# Schmetic.net
KiCad netlist of a schematic drawn in EAGLE
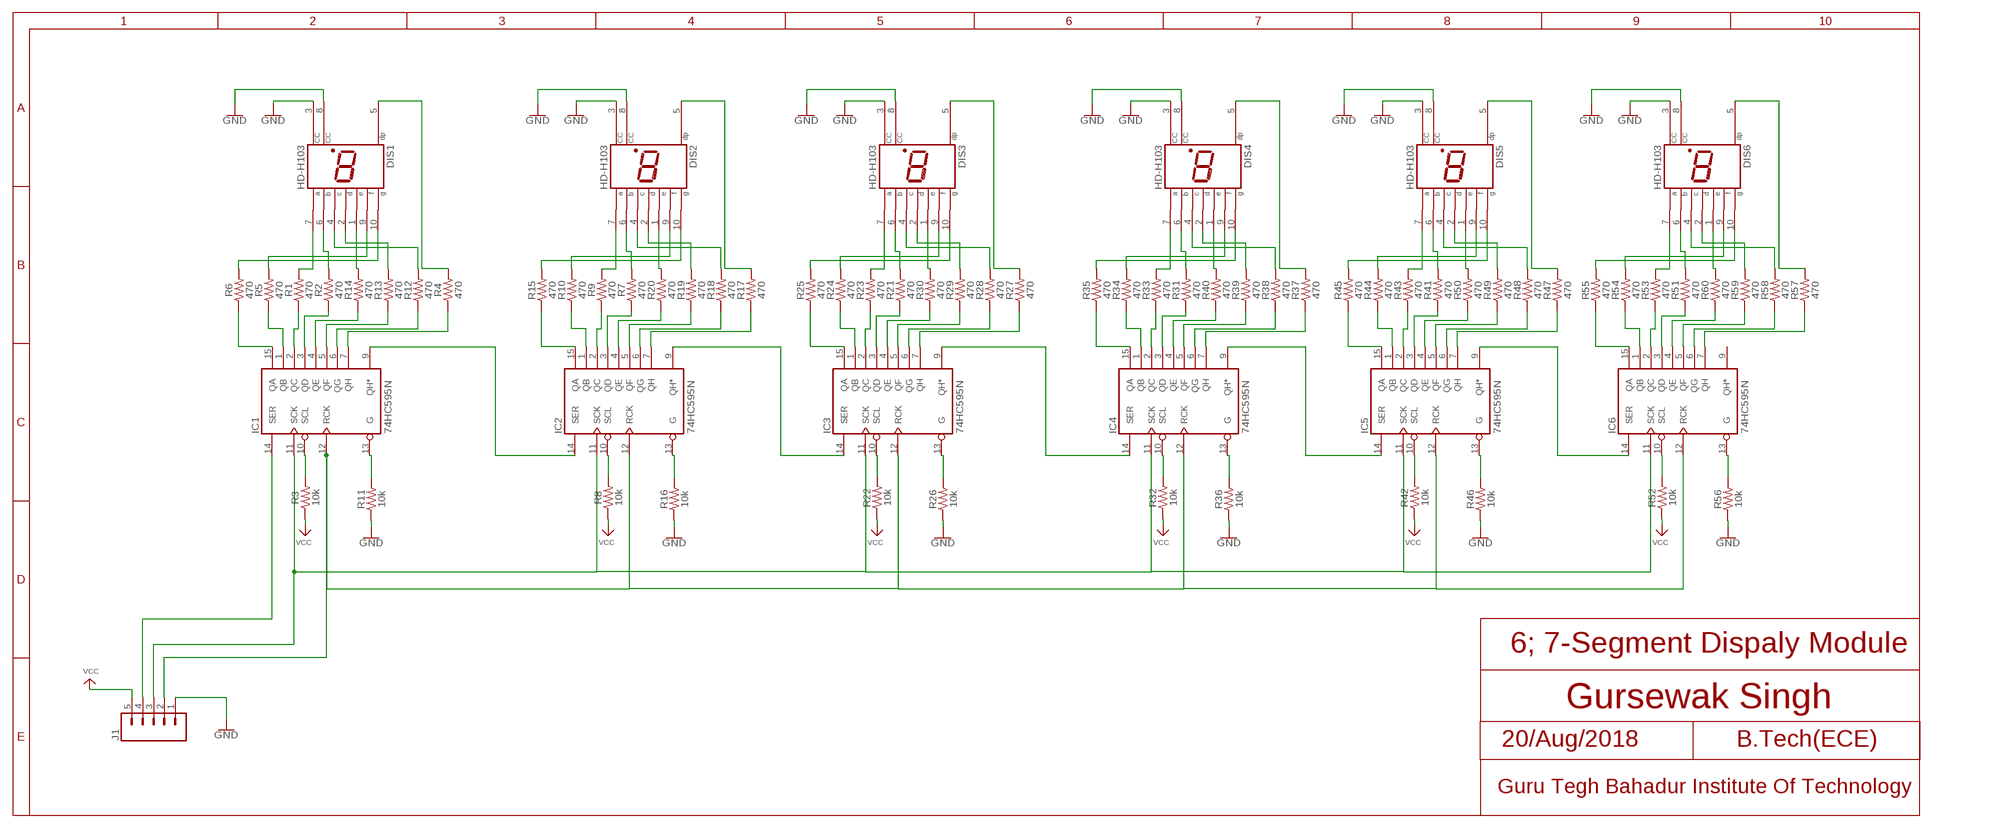
[diagram p0: schematic, sheet 1]

(export (version "E")
  (design (tool "Eeschema 10.0.6"))
  (components
    (comp (ref "DIS1")
      (value "HD-H103")
      (footprint "eagle-import:HDSP-M")
      (libsource (lib "eagle-import") (part "HD-H103"))
    )
    (comp (ref "DIS2")
      (value "HD-H103")
      (footprint "eagle-import:HDSP-M")
      (libsource (lib "eagle-import") (part "HD-H103"))
    )
    (comp (ref "DIS3")
      (value "HD-H103")
      (footprint "eagle-import:HDSP-M")
      (libsource (lib "eagle-import") (part "HD-H103"))
    )
    (comp (ref "DIS4")
      (value "HD-H103")
      (footprint "eagle-import:HDSP-M")
      (libsource (lib "eagle-import") (part "HD-H103"))
    )
    (comp (ref "DIS5")
      (value "HD-H103")
      (footprint "eagle-import:HDSP-M")
      (libsource (lib "eagle-import") (part "HD-H103"))
    )
    (comp (ref "DIS6")
      (value "HD-H103")
      (footprint "eagle-import:HDSP-M")
      (libsource (lib "eagle-import") (part "HD-H103"))
    )
    (comp (ref "IC1")
      (value "74HC595N")
      (footprint "eagle-import:DIL16")
      (libsource (lib "eagle-import") (part "74595NHC"))
    )
    (comp (ref "IC2")
      (value "74HC595N")
      (footprint "eagle-import:DIL16")
      (libsource (lib "eagle-import") (part "74595NHC"))
    )
    (comp (ref "IC3")
      (value "74HC595N")
      (footprint "eagle-import:DIL16")
      (libsource (lib "eagle-import") (part "74595NHC"))
    )
    (comp (ref "IC4")
      (value "74HC595N")
      (footprint "eagle-import:DIL16")
      (libsource (lib "eagle-import") (part "74595NHC"))
    )
    (comp (ref "IC5")
      (value "74HC595N")
      (footprint "eagle-import:DIL16")
      (libsource (lib "eagle-import") (part "74595NHC"))
    )
    (comp (ref "IC6")
      (value "74HC595N")
      (footprint "eagle-import:DIL16")
      (libsource (lib "eagle-import") (part "74595NHC"))
    )
    (comp (ref "J1")
      (value "CONN_05LOCK_LONGPADS")
      (footprint "eagle-import:1X05_LOCK_LONGPADS")
      (libsource (lib "eagle-import") (part "CONN_05LOCK_LONGPADS"))
    )
    (comp (ref "R1")
      (value "470")
      (footprint "eagle-import:AXIAL-0.3")
      (libsource (lib "eagle-import") (part "1KOHM-HORIZ-1/4W-1%"))
    )
    (comp (ref "R2")
      (value "470")
      (footprint "eagle-import:AXIAL-0.3")
      (libsource (lib "eagle-import") (part "1KOHM-HORIZ-1/4W-1%"))
    )
    (comp (ref "R3")
      (value "10k")
      (footprint "eagle-import:AXIAL-0.3")
      (libsource (lib "eagle-import") (part "1KOHM-HORIZ-1/4W-1%"))
    )
    (comp (ref "R4")
      (value "470")
      (footprint "eagle-import:AXIAL-0.3")
      (libsource (lib "eagle-import") (part "1KOHM-HORIZ-1/4W-1%"))
    )
    (comp (ref "R5")
      (value "470")
      (footprint "eagle-import:AXIAL-0.3")
      (libsource (lib "eagle-import") (part "1KOHM-HORIZ-1/4W-1%"))
    )
    (comp (ref "R6")
      (value "470")
      (footprint "eagle-import:AXIAL-0.3")
      (libsource (lib "eagle-import") (part "1KOHM-HORIZ-1/4W-1%"))
    )
    (comp (ref "R7")
      (value "470")
      (footprint "eagle-import:AXIAL-0.3")
      (libsource (lib "eagle-import") (part "1KOHM-HORIZ-1/4W-1%"))
    )
    (comp (ref "R8")
      (value "10k")
      (footprint "eagle-import:AXIAL-0.3")
      (libsource (lib "eagle-import") (part "1KOHM-HORIZ-1/4W-1%"))
    )
    (comp (ref "R9")
      (value "470")
      (footprint "eagle-import:AXIAL-0.3")
      (libsource (lib "eagle-import") (part "1KOHM-HORIZ-1/4W-1%"))
    )
    (comp (ref "R10")
      (value "470")
      (footprint "eagle-import:AXIAL-0.3")
      (libsource (lib "eagle-import") (part "1KOHM-HORIZ-1/4W-1%"))
    )
    (comp (ref "R11")
      (value "10k")
      (footprint "eagle-import:AXIAL-0.3")
      (libsource (lib "eagle-import") (part "1KOHM-HORIZ-1/4W-1%"))
    )
    (comp (ref "R12")
      (value "470")
      (footprint "eagle-import:AXIAL-0.3")
      (libsource (lib "eagle-import") (part "1KOHM-HORIZ-1/4W-1%"))
    )
    (comp (ref "R13")
      (value "470")
      (footprint "eagle-import:AXIAL-0.3")
      (libsource (lib "eagle-import") (part "1KOHM-HORIZ-1/4W-1%"))
    )
    (comp (ref "R14")
      (value "470")
      (footprint "eagle-import:AXIAL-0.3")
      (libsource (lib "eagle-import") (part "1KOHM-HORIZ-1/4W-1%"))
    )
    (comp (ref "R15")
      (value "470")
      (footprint "eagle-import:AXIAL-0.3")
      (libsource (lib "eagle-import") (part "1KOHM-HORIZ-1/4W-1%"))
    )
    (comp (ref "R16")
      (value "10k")
      (footprint "eagle-import:AXIAL-0.3")
      (libsource (lib "eagle-import") (part "1KOHM-HORIZ-1/4W-1%"))
    )
    (comp (ref "R17")
      (value "470")
      (footprint "eagle-import:AXIAL-0.3")
      (libsource (lib "eagle-import") (part "1KOHM-HORIZ-1/4W-1%"))
    )
    (comp (ref "R18")
      (value "470")
      (footprint "eagle-import:AXIAL-0.3")
      (libsource (lib "eagle-import") (part "1KOHM-HORIZ-1/4W-1%"))
    )
    (comp (ref "R19")
      (value "470")
      (footprint "eagle-import:AXIAL-0.3")
      (libsource (lib "eagle-import") (part "1KOHM-HORIZ-1/4W-1%"))
    )
    (comp (ref "R20")
      (value "470")
      (footprint "eagle-import:AXIAL-0.3")
      (libsource (lib "eagle-import") (part "1KOHM-HORIZ-1/4W-1%"))
    )
    (comp (ref "R21")
      (value "470")
      (footprint "eagle-import:AXIAL-0.3")
      (libsource (lib "eagle-import") (part "1KOHM-HORIZ-1/4W-1%"))
    )
    (comp (ref "R22")
      (value "10k")
      (footprint "eagle-import:AXIAL-0.3")
      (libsource (lib "eagle-import") (part "1KOHM-HORIZ-1/4W-1%"))
    )
    (comp (ref "R23")
      (value "470")
      (footprint "eagle-import:AXIAL-0.3")
      (libsource (lib "eagle-import") (part "1KOHM-HORIZ-1/4W-1%"))
    )
    (comp (ref "R24")
      (value "470")
      (footprint "eagle-import:AXIAL-0.3")
      (libsource (lib "eagle-import") (part "1KOHM-HORIZ-1/4W-1%"))
    )
    (comp (ref "R25")
      (value "470")
      (footprint "eagle-import:AXIAL-0.3")
      (libsource (lib "eagle-import") (part "1KOHM-HORIZ-1/4W-1%"))
    )
    (comp (ref "R26")
      (value "10k")
      (footprint "eagle-import:AXIAL-0.3")
      (libsource (lib "eagle-import") (part "1KOHM-HORIZ-1/4W-1%"))
    )
    (comp (ref "R27")
      (value "470")
      (footprint "eagle-import:AXIAL-0.3")
      (libsource (lib "eagle-import") (part "1KOHM-HORIZ-1/4W-1%"))
    )
    (comp (ref "R28")
      (value "470")
      (footprint "eagle-import:AXIAL-0.3")
      (libsource (lib "eagle-import") (part "1KOHM-HORIZ-1/4W-1%"))
    )
    (comp (ref "R29")
      (value "470")
      (footprint "eagle-import:AXIAL-0.3")
      (libsource (lib "eagle-import") (part "1KOHM-HORIZ-1/4W-1%"))
    )
    (comp (ref "R30")
      (value "470")
      (footprint "eagle-import:AXIAL-0.3")
      (libsource (lib "eagle-import") (part "1KOHM-HORIZ-1/4W-1%"))
    )
    (comp (ref "R31")
      (value "470")
      (footprint "eagle-import:AXIAL-0.3")
      (libsource (lib "eagle-import") (part "1KOHM-HORIZ-1/4W-1%"))
    )
    (comp (ref "R32")
      (value "10k")
      (footprint "eagle-import:AXIAL-0.3")
      (libsource (lib "eagle-import") (part "1KOHM-HORIZ-1/4W-1%"))
    )
    (comp (ref "R33")
      (value "470")
      (footprint "eagle-import:AXIAL-0.3")
      (libsource (lib "eagle-import") (part "1KOHM-HORIZ-1/4W-1%"))
    )
    (comp (ref "R34")
      (value "470")
      (footprint "eagle-import:AXIAL-0.3")
      (libsource (lib "eagle-import") (part "1KOHM-HORIZ-1/4W-1%"))
    )
    (comp (ref "R35")
      (value "470")
      (footprint "eagle-import:AXIAL-0.3")
      (libsource (lib "eagle-import") (part "1KOHM-HORIZ-1/4W-1%"))
    )
    (comp (ref "R36")
      (value "10k")
      (footprint "eagle-import:AXIAL-0.3")
      (libsource (lib "eagle-import") (part "1KOHM-HORIZ-1/4W-1%"))
    )
    (comp (ref "R37")
      (value "470")
      (footprint "eagle-import:AXIAL-0.3")
      (libsource (lib "eagle-import") (part "1KOHM-HORIZ-1/4W-1%"))
    )
    (comp (ref "R38")
      (value "470")
      (footprint "eagle-import:AXIAL-0.3")
      (libsource (lib "eagle-import") (part "1KOHM-HORIZ-1/4W-1%"))
    )
    (comp (ref "R39")
      (value "470")
      (footprint "eagle-import:AXIAL-0.3")
      (libsource (lib "eagle-import") (part "1KOHM-HORIZ-1/4W-1%"))
    )
    (comp (ref "R40")
      (value "470")
      (footprint "eagle-import:AXIAL-0.3")
      (libsource (lib "eagle-import") (part "1KOHM-HORIZ-1/4W-1%"))
    )
    (comp (ref "R41")
      (value "470")
      (footprint "eagle-import:AXIAL-0.3")
      (libsource (lib "eagle-import") (part "1KOHM-HORIZ-1/4W-1%"))
    )
    (comp (ref "R42")
      (value "10k")
      (footprint "eagle-import:AXIAL-0.3")
      (libsource (lib "eagle-import") (part "1KOHM-HORIZ-1/4W-1%"))
    )
    (comp (ref "R43")
      (value "470")
      (footprint "eagle-import:AXIAL-0.3")
      (libsource (lib "eagle-import") (part "1KOHM-HORIZ-1/4W-1%"))
    )
    (comp (ref "R44")
      (value "470")
      (footprint "eagle-import:AXIAL-0.3")
      (libsource (lib "eagle-import") (part "1KOHM-HORIZ-1/4W-1%"))
    )
    (comp (ref "R45")
      (value "470")
      (footprint "eagle-import:AXIAL-0.3")
      (libsource (lib "eagle-import") (part "1KOHM-HORIZ-1/4W-1%"))
    )
    (comp (ref "R46")
      (value "10k")
      (footprint "eagle-import:AXIAL-0.3")
      (libsource (lib "eagle-import") (part "1KOHM-HORIZ-1/4W-1%"))
    )
    (comp (ref "R47")
      (value "470")
      (footprint "eagle-import:AXIAL-0.3")
      (libsource (lib "eagle-import") (part "1KOHM-HORIZ-1/4W-1%"))
    )
    (comp (ref "R48")
      (value "470")
      (footprint "eagle-import:AXIAL-0.3")
      (libsource (lib "eagle-import") (part "1KOHM-HORIZ-1/4W-1%"))
    )
    (comp (ref "R49")
      (value "470")
      (footprint "eagle-import:AXIAL-0.3")
      (libsource (lib "eagle-import") (part "1KOHM-HORIZ-1/4W-1%"))
    )
    (comp (ref "R50")
      (value "470")
      (footprint "eagle-import:AXIAL-0.3")
      (libsource (lib "eagle-import") (part "1KOHM-HORIZ-1/4W-1%"))
    )
    (comp (ref "R51")
      (value "470")
      (footprint "eagle-import:AXIAL-0.3")
      (libsource (lib "eagle-import") (part "1KOHM-HORIZ-1/4W-1%"))
    )
    (comp (ref "R52")
      (value "10k")
      (footprint "eagle-import:AXIAL-0.3")
      (libsource (lib "eagle-import") (part "1KOHM-HORIZ-1/4W-1%"))
    )
    (comp (ref "R53")
      (value "470")
      (footprint "eagle-import:AXIAL-0.3")
      (libsource (lib "eagle-import") (part "1KOHM-HORIZ-1/4W-1%"))
    )
    (comp (ref "R54")
      (value "470")
      (footprint "eagle-import:AXIAL-0.3")
      (libsource (lib "eagle-import") (part "1KOHM-HORIZ-1/4W-1%"))
    )
    (comp (ref "R55")
      (value "470")
      (footprint "eagle-import:AXIAL-0.3")
      (libsource (lib "eagle-import") (part "1KOHM-HORIZ-1/4W-1%"))
    )
    (comp (ref "R56")
      (value "10k")
      (footprint "eagle-import:AXIAL-0.3")
      (libsource (lib "eagle-import") (part "1KOHM-HORIZ-1/4W-1%"))
    )
    (comp (ref "R57")
      (value "470")
      (footprint "eagle-import:AXIAL-0.3")
      (libsource (lib "eagle-import") (part "1KOHM-HORIZ-1/4W-1%"))
    )
    (comp (ref "R58")
      (value "470")
      (footprint "eagle-import:AXIAL-0.3")
      (libsource (lib "eagle-import") (part "1KOHM-HORIZ-1/4W-1%"))
    )
    (comp (ref "R59")
      (value "470")
      (footprint "eagle-import:AXIAL-0.3")
      (libsource (lib "eagle-import") (part "1KOHM-HORIZ-1/4W-1%"))
    )
    (comp (ref "R60")
      (value "470")
      (footprint "eagle-import:AXIAL-0.3")
      (libsource (lib "eagle-import") (part "1KOHM-HORIZ-1/4W-1%"))
    )
  )
  (nets
    (net (code "1") (name "GND") (class "Default")
      (node (ref "DIS1") (pin "3") (pinfunction "CC_3") (pintype "passive"))
      (node (ref "DIS1") (pin "8") (pinfunction "CC_8") (pintype "passive"))
      (node (ref "DIS2") (pin "3") (pinfunction "CC_3") (pintype "passive"))
      (node (ref "DIS2") (pin "8") (pinfunction "CC_8") (pintype "passive"))
      (node (ref "DIS3") (pin "3") (pinfunction "CC_3") (pintype "passive"))
      (node (ref "DIS3") (pin "8") (pinfunction "CC_8") (pintype "passive"))
      (node (ref "DIS4") (pin "3") (pinfunction "CC_3") (pintype "passive"))
      (node (ref "DIS4") (pin "8") (pinfunction "CC_8") (pintype "passive"))
      (node (ref "DIS5") (pin "3") (pinfunction "CC_3") (pintype "passive"))
      (node (ref "DIS5") (pin "8") (pinfunction "CC_8") (pintype "passive"))
      (node (ref "DIS6") (pin "3") (pinfunction "CC_3") (pintype "passive"))
      (node (ref "DIS6") (pin "8") (pinfunction "CC_8") (pintype "passive"))
      (node (ref "J1") (pin "1") (pinfunction "1_1") (pintype "passive"))
      (node (ref "R11") (pin "P$1") (pinfunction "1_P$1") (pintype "passive"))
      (node (ref "R16") (pin "P$1") (pinfunction "1_P$1") (pintype "passive"))
      (node (ref "R26") (pin "P$1") (pinfunction "1_P$1") (pintype "passive"))
      (node (ref "R36") (pin "P$1") (pinfunction "1_P$1") (pintype "passive"))
      (node (ref "R46") (pin "P$1") (pinfunction "1_P$1") (pintype "passive"))
      (node (ref "R56") (pin "P$1") (pinfunction "1_P$1") (pintype "passive"))
    )
    (net (code "2") (name "Net-(DIS1-A)") (class "Default")
      (node (ref "DIS1") (pin "7") (pinfunction "A_7") (pintype "passive"))
      (node (ref "R1") (pin "P$2") (pinfunction "2_P$2") (pintype "passive"))
    )
    (net (code "3") (name "Net-(DIS1-B)") (class "Default")
      (node (ref "DIS1") (pin "6") (pinfunction "B_6") (pintype "passive"))
      (node (ref "R2") (pin "P$2") (pinfunction "2_P$2") (pintype "passive"))
    )
    (net (code "4") (name "Net-(DIS1-C)") (class "Default")
      (node (ref "DIS1") (pin "4") (pinfunction "C_4") (pintype "passive"))
      (node (ref "R12") (pin "P$2") (pinfunction "2_P$2") (pintype "passive"))
    )
    (net (code "5") (name "Net-(DIS1-D)") (class "Default")
      (node (ref "DIS1") (pin "2") (pinfunction "D_2") (pintype "passive"))
      (node (ref "R13") (pin "P$2") (pinfunction "2_P$2") (pintype "passive"))
    )
    (net (code "6") (name "Net-(DIS1-DP)") (class "Default")
      (node (ref "DIS1") (pin "5") (pinfunction "DP_5") (pintype "passive"))
      (node (ref "R4") (pin "P$2") (pinfunction "2_P$2") (pintype "passive"))
    )
    (net (code "7") (name "Net-(DIS1-E)") (class "Default")
      (node (ref "DIS1") (pin "1") (pinfunction "E_1") (pintype "passive"))
      (node (ref "R14") (pin "P$2") (pinfunction "2_P$2") (pintype "passive"))
    )
    (net (code "8") (name "Net-(DIS1-F)") (class "Default")
      (node (ref "DIS1") (pin "9") (pinfunction "F_9") (pintype "passive"))
      (node (ref "R5") (pin "P$2") (pinfunction "2_P$2") (pintype "passive"))
    )
    (net (code "9") (name "Net-(DIS1-G)") (class "Default")
      (node (ref "DIS1") (pin "10") (pinfunction "G_10") (pintype "passive"))
      (node (ref "R6") (pin "P$2") (pinfunction "2_P$2") (pintype "passive"))
    )
    (net (code "10") (name "Net-(DIS2-A)") (class "Default")
      (node (ref "DIS2") (pin "7") (pinfunction "A_7") (pintype "passive"))
      (node (ref "R9") (pin "P$2") (pinfunction "2_P$2") (pintype "passive"))
    )
    (net (code "11") (name "Net-(DIS2-B)") (class "Default")
      (node (ref "DIS2") (pin "6") (pinfunction "B_6") (pintype "passive"))
      (node (ref "R7") (pin "P$2") (pinfunction "2_P$2") (pintype "passive"))
    )
    (net (code "12") (name "Net-(DIS2-C)") (class "Default")
      (node (ref "DIS2") (pin "4") (pinfunction "C_4") (pintype "passive"))
      (node (ref "R18") (pin "P$2") (pinfunction "2_P$2") (pintype "passive"))
    )
    (net (code "13") (name "Net-(DIS2-D)") (class "Default")
      (node (ref "DIS2") (pin "2") (pinfunction "D_2") (pintype "passive"))
      (node (ref "R19") (pin "P$2") (pinfunction "2_P$2") (pintype "passive"))
    )
    (net (code "14") (name "Net-(DIS2-DP)") (class "Default")
      (node (ref "DIS2") (pin "5") (pinfunction "DP_5") (pintype "passive"))
      (node (ref "R17") (pin "P$2") (pinfunction "2_P$2") (pintype "passive"))
    )
    (net (code "15") (name "Net-(DIS2-E)") (class "Default")
      (node (ref "DIS2") (pin "1") (pinfunction "E_1") (pintype "passive"))
      (node (ref "R20") (pin "P$2") (pinfunction "2_P$2") (pintype "passive"))
    )
    (net (code "16") (name "Net-(DIS2-F)") (class "Default")
      (node (ref "DIS2") (pin "9") (pinfunction "F_9") (pintype "passive"))
      (node (ref "R10") (pin "P$2") (pinfunction "2_P$2") (pintype "passive"))
    )
    (net (code "17") (name "Net-(DIS2-G)") (class "Default")
      (node (ref "DIS2") (pin "10") (pinfunction "G_10") (pintype "passive"))
      (node (ref "R15") (pin "P$2") (pinfunction "2_P$2") (pintype "passive"))
    )
    (net (code "18") (name "Net-(DIS3-A)") (class "Default")
      (node (ref "DIS3") (pin "7") (pinfunction "A_7") (pintype "passive"))
      (node (ref "R23") (pin "P$2") (pinfunction "2_P$2") (pintype "passive"))
    )
    (net (code "19") (name "Net-(DIS3-B)") (class "Default")
      (node (ref "DIS3") (pin "6") (pinfunction "B_6") (pintype "passive"))
      (node (ref "R21") (pin "P$2") (pinfunction "2_P$2") (pintype "passive"))
    )
    (net (code "20") (name "Net-(DIS3-C)") (class "Default")
      (node (ref "DIS3") (pin "4") (pinfunction "C_4") (pintype "passive"))
      (node (ref "R28") (pin "P$2") (pinfunction "2_P$2") (pintype "passive"))
    )
    (net (code "21") (name "Net-(DIS3-D)") (class "Default")
      (node (ref "DIS3") (pin "2") (pinfunction "D_2") (pintype "passive"))
      (node (ref "R29") (pin "P$2") (pinfunction "2_P$2") (pintype "passive"))
    )
    (net (code "22") (name "Net-(DIS3-DP)") (class "Default")
      (node (ref "DIS3") (pin "5") (pinfunction "DP_5") (pintype "passive"))
      (node (ref "R27") (pin "P$2") (pinfunction "2_P$2") (pintype "passive"))
    )
    (net (code "23") (name "Net-(DIS3-E)") (class "Default")
      (node (ref "DIS3") (pin "1") (pinfunction "E_1") (pintype "passive"))
      (node (ref "R30") (pin "P$2") (pinfunction "2_P$2") (pintype "passive"))
    )
    (net (code "24") (name "Net-(DIS3-F)") (class "Default")
      (node (ref "DIS3") (pin "9") (pinfunction "F_9") (pintype "passive"))
      (node (ref "R24") (pin "P$2") (pinfunction "2_P$2") (pintype "passive"))
    )
    (net (code "25") (name "Net-(DIS3-G)") (class "Default")
      (node (ref "DIS3") (pin "10") (pinfunction "G_10") (pintype "passive"))
      (node (ref "R25") (pin "P$2") (pinfunction "2_P$2") (pintype "passive"))
    )
    (net (code "26") (name "Net-(DIS4-A)") (class "Default")
      (node (ref "DIS4") (pin "7") (pinfunction "A_7") (pintype "passive"))
      (node (ref "R33") (pin "P$2") (pinfunction "2_P$2") (pintype "passive"))
    )
    (net (code "27") (name "Net-(DIS4-B)") (class "Default")
      (node (ref "DIS4") (pin "6") (pinfunction "B_6") (pintype "passive"))
      (node (ref "R31") (pin "P$2") (pinfunction "2_P$2") (pintype "passive"))
    )
    (net (code "28") (name "Net-(DIS4-C)") (class "Default")
      (node (ref "DIS4") (pin "4") (pinfunction "C_4") (pintype "passive"))
      (node (ref "R38") (pin "P$2") (pinfunction "2_P$2") (pintype "passive"))
    )
    (net (code "29") (name "Net-(DIS4-D)") (class "Default")
      (node (ref "DIS4") (pin "2") (pinfunction "D_2") (pintype "passive"))
      (node (ref "R39") (pin "P$2") (pinfunction "2_P$2") (pintype "passive"))
    )
    (net (code "30") (name "Net-(DIS4-DP)") (class "Default")
      (node (ref "DIS4") (pin "5") (pinfunction "DP_5") (pintype "passive"))
      (node (ref "R37") (pin "P$2") (pinfunction "2_P$2") (pintype "passive"))
    )
    (net (code "31") (name "Net-(DIS4-E)") (class "Default")
      (node (ref "DIS4") (pin "1") (pinfunction "E_1") (pintype "passive"))
      (node (ref "R40") (pin "P$2") (pinfunction "2_P$2") (pintype "passive"))
    )
    (net (code "32") (name "Net-(DIS4-F)") (class "Default")
      (node (ref "DIS4") (pin "9") (pinfunction "F_9") (pintype "passive"))
      (node (ref "R34") (pin "P$2") (pinfunction "2_P$2") (pintype "passive"))
    )
    (net (code "33") (name "Net-(DIS4-G)") (class "Default")
      (node (ref "DIS4") (pin "10") (pinfunction "G_10") (pintype "passive"))
      (node (ref "R35") (pin "P$2") (pinfunction "2_P$2") (pintype "passive"))
    )
    (net (code "34") (name "Net-(DIS5-A)") (class "Default")
      (node (ref "DIS5") (pin "7") (pinfunction "A_7") (pintype "passive"))
      (node (ref "R43") (pin "P$2") (pinfunction "2_P$2") (pintype "passive"))
    )
    (net (code "35") (name "Net-(DIS5-B)") (class "Default")
      (node (ref "DIS5") (pin "6") (pinfunction "B_6") (pintype "passive"))
      (node (ref "R41") (pin "P$2") (pinfunction "2_P$2") (pintype "passive"))
    )
    (net (code "36") (name "Net-(DIS5-C)") (class "Default")
      (node (ref "DIS5") (pin "4") (pinfunction "C_4") (pintype "passive"))
      (node (ref "R48") (pin "P$2") (pinfunction "2_P$2") (pintype "passive"))
    )
    (net (code "37") (name "Net-(DIS5-D)") (class "Default")
      (node (ref "DIS5") (pin "2") (pinfunction "D_2") (pintype "passive"))
      (node (ref "R49") (pin "P$2") (pinfunction "2_P$2") (pintype "passive"))
    )
    (net (code "38") (name "Net-(DIS5-DP)") (class "Default")
      (node (ref "DIS5") (pin "5") (pinfunction "DP_5") (pintype "passive"))
      (node (ref "R47") (pin "P$2") (pinfunction "2_P$2") (pintype "passive"))
    )
    (net (code "39") (name "Net-(DIS5-E)") (class "Default")
      (node (ref "DIS5") (pin "1") (pinfunction "E_1") (pintype "passive"))
      (node (ref "R50") (pin "P$2") (pinfunction "2_P$2") (pintype "passive"))
    )
    (net (code "40") (name "Net-(DIS5-F)") (class "Default")
      (node (ref "DIS5") (pin "9") (pinfunction "F_9") (pintype "passive"))
      (node (ref "R44") (pin "P$2") (pinfunction "2_P$2") (pintype "passive"))
    )
    (net (code "41") (name "Net-(DIS5-G)") (class "Default")
      (node (ref "DIS5") (pin "10") (pinfunction "G_10") (pintype "passive"))
      (node (ref "R45") (pin "P$2") (pinfunction "2_P$2") (pintype "passive"))
    )
    (net (code "42") (name "Net-(DIS6-A)") (class "Default")
      (node (ref "DIS6") (pin "7") (pinfunction "A_7") (pintype "passive"))
      (node (ref "R53") (pin "P$2") (pinfunction "2_P$2") (pintype "passive"))
    )
    (net (code "43") (name "Net-(DIS6-B)") (class "Default")
      (node (ref "DIS6") (pin "6") (pinfunction "B_6") (pintype "passive"))
      (node (ref "R51") (pin "P$2") (pinfunction "2_P$2") (pintype "passive"))
    )
    (net (code "44") (name "Net-(DIS6-C)") (class "Default")
      (node (ref "DIS6") (pin "4") (pinfunction "C_4") (pintype "passive"))
      (node (ref "R58") (pin "P$2") (pinfunction "2_P$2") (pintype "passive"))
    )
    (net (code "45") (name "Net-(DIS6-D)") (class "Default")
      (node (ref "DIS6") (pin "2") (pinfunction "D_2") (pintype "passive"))
      (node (ref "R59") (pin "P$2") (pinfunction "2_P$2") (pintype "passive"))
    )
    (net (code "46") (name "Net-(DIS6-DP)") (class "Default")
      (node (ref "DIS6") (pin "5") (pinfunction "DP_5") (pintype "passive"))
      (node (ref "R57") (pin "P$2") (pinfunction "2_P$2") (pintype "passive"))
    )
    (net (code "47") (name "Net-(DIS6-E)") (class "Default")
      (node (ref "DIS6") (pin "1") (pinfunction "E_1") (pintype "passive"))
      (node (ref "R60") (pin "P$2") (pinfunction "2_P$2") (pintype "passive"))
    )
    (net (code "48") (name "Net-(DIS6-F)") (class "Default")
      (node (ref "DIS6") (pin "9") (pinfunction "F_9") (pintype "passive"))
      (node (ref "R54") (pin "P$2") (pinfunction "2_P$2") (pintype "passive"))
    )
    (net (code "49") (name "Net-(DIS6-G)") (class "Default")
      (node (ref "DIS6") (pin "10") (pinfunction "G_10") (pintype "passive"))
      (node (ref "R55") (pin "P$2") (pinfunction "2_P$2") (pintype "passive"))
    )
    (net (code "50") (name "Net-(IC1A-G)") (class "Default")
      (node (ref "IC1") (pin "13") (pinfunction "G_13") (pintype "input"))
      (node (ref "R11") (pin "P$2") (pinfunction "2_P$2") (pintype "passive"))
    )
    (net (code "51") (name "Net-(IC1A-QA)") (class "Default")
      (node (ref "IC1") (pin "15") (pinfunction "QA_15") (pintype "tri_state"))
      (node (ref "R6") (pin "P$1") (pinfunction "1_P$1") (pintype "passive"))
    )
    (net (code "52") (name "Net-(IC1A-QB)") (class "Default")
      (node (ref "IC1") (pin "1") (pinfunction "QB_1") (pintype "tri_state"))
      (node (ref "R5") (pin "P$1") (pinfunction "1_P$1") (pintype "passive"))
    )
    (net (code "53") (name "Net-(IC1A-QC)") (class "Default")
      (node (ref "IC1") (pin "2") (pinfunction "QC_2") (pintype "tri_state"))
      (node (ref "R1") (pin "P$1") (pinfunction "1_P$1") (pintype "passive"))
    )
    (net (code "54") (name "Net-(IC1A-QD)") (class "Default")
      (node (ref "IC1") (pin "3") (pinfunction "QD_3") (pintype "tri_state"))
      (node (ref "R2") (pin "P$1") (pinfunction "1_P$1") (pintype "passive"))
    )
    (net (code "55") (name "Net-(IC1A-QE)") (class "Default")
      (node (ref "IC1") (pin "4") (pinfunction "QE_4") (pintype "tri_state"))
      (node (ref "R14") (pin "P$1") (pinfunction "1_P$1") (pintype "passive"))
    )
    (net (code "56") (name "Net-(IC1A-QF)") (class "Default")
      (node (ref "IC1") (pin "5") (pinfunction "QF_5") (pintype "tri_state"))
      (node (ref "R13") (pin "P$1") (pinfunction "1_P$1") (pintype "passive"))
    )
    (net (code "57") (name "Net-(IC1A-QG)") (class "Default")
      (node (ref "IC1") (pin "6") (pinfunction "QG_6") (pintype "tri_state"))
      (node (ref "R12") (pin "P$1") (pinfunction "1_P$1") (pintype "passive"))
    )
    (net (code "58") (name "Net-(IC1A-QH)") (class "Default")
      (node (ref "IC1") (pin "7") (pinfunction "QH_7") (pintype "tri_state"))
      (node (ref "R4") (pin "P$1") (pinfunction "1_P$1") (pintype "passive"))
    )
    (net (code "59") (name "Net-(IC1A-QH*)") (class "Default")
      (node (ref "IC1") (pin "9") (pinfunction "QH*_9") (pintype "tri_state"))
      (node (ref "IC2") (pin "14") (pinfunction "SER_14") (pintype "input"))
    )
    (net (code "60") (name "Net-(IC1A-RCK)") (class "Default")
      (node (ref "IC1") (pin "12") (pinfunction "RCK_12") (pintype "input"))
      (node (ref "IC2") (pin "12") (pinfunction "RCK_12") (pintype "input"))
      (node (ref "IC3") (pin "12") (pinfunction "RCK_12") (pintype "input"))
      (node (ref "IC4") (pin "12") (pinfunction "RCK_12") (pintype "input"))
      (node (ref "IC5") (pin "12") (pinfunction "RCK_12") (pintype "input"))
      (node (ref "IC6") (pin "12") (pinfunction "RCK_12") (pintype "input"))
      (node (ref "J1") (pin "2") (pinfunction "2_2") (pintype "passive"))
    )
    (net (code "61") (name "Net-(IC1A-SCK)") (class "Default")
      (node (ref "IC1") (pin "11") (pinfunction "SCK_11") (pintype "input"))
      (node (ref "IC2") (pin "11") (pinfunction "SCK_11") (pintype "input"))
      (node (ref "IC3") (pin "11") (pinfunction "SCK_11") (pintype "input"))
      (node (ref "IC4") (pin "11") (pinfunction "SCK_11") (pintype "input"))
      (node (ref "IC5") (pin "11") (pinfunction "SCK_11") (pintype "input"))
      (node (ref "IC6") (pin "11") (pinfunction "SCK_11") (pintype "input"))
      (node (ref "J1") (pin "3") (pinfunction "3_3") (pintype "passive"))
    )
    (net (code "62") (name "Net-(IC1A-SCL)") (class "Default")
      (node (ref "IC1") (pin "10") (pinfunction "SCL_10") (pintype "input"))
      (node (ref "R3") (pin "P$2") (pinfunction "2_P$2") (pintype "passive"))
    )
    (net (code "63") (name "Net-(IC1A-SER)") (class "Default")
      (node (ref "IC1") (pin "14") (pinfunction "SER_14") (pintype "input"))
      (node (ref "J1") (pin "4") (pinfunction "4_4") (pintype "passive"))
    )
    (net (code "64") (name "Net-(IC2A-G)") (class "Default")
      (node (ref "IC2") (pin "13") (pinfunction "G_13") (pintype "input"))
      (node (ref "R16") (pin "P$2") (pinfunction "2_P$2") (pintype "passive"))
    )
    (net (code "65") (name "Net-(IC2A-QA)") (class "Default")
      (node (ref "IC2") (pin "15") (pinfunction "QA_15") (pintype "tri_state"))
      (node (ref "R15") (pin "P$1") (pinfunction "1_P$1") (pintype "passive"))
    )
    (net (code "66") (name "Net-(IC2A-QB)") (class "Default")
      (node (ref "IC2") (pin "1") (pinfunction "QB_1") (pintype "tri_state"))
      (node (ref "R10") (pin "P$1") (pinfunction "1_P$1") (pintype "passive"))
    )
    (net (code "67") (name "Net-(IC2A-QC)") (class "Default")
      (node (ref "IC2") (pin "2") (pinfunction "QC_2") (pintype "tri_state"))
      (node (ref "R9") (pin "P$1") (pinfunction "1_P$1") (pintype "passive"))
    )
    (net (code "68") (name "Net-(IC2A-QD)") (class "Default")
      (node (ref "IC2") (pin "3") (pinfunction "QD_3") (pintype "tri_state"))
      (node (ref "R7") (pin "P$1") (pinfunction "1_P$1") (pintype "passive"))
    )
    (net (code "69") (name "Net-(IC2A-QE)") (class "Default")
      (node (ref "IC2") (pin "4") (pinfunction "QE_4") (pintype "tri_state"))
      (node (ref "R20") (pin "P$1") (pinfunction "1_P$1") (pintype "passive"))
    )
    (net (code "70") (name "Net-(IC2A-QF)") (class "Default")
      (node (ref "IC2") (pin "5") (pinfunction "QF_5") (pintype "tri_state"))
      (node (ref "R19") (pin "P$1") (pinfunction "1_P$1") (pintype "passive"))
    )
    (net (code "71") (name "Net-(IC2A-QG)") (class "Default")
      (node (ref "IC2") (pin "6") (pinfunction "QG_6") (pintype "tri_state"))
      (node (ref "R18") (pin "P$1") (pinfunction "1_P$1") (pintype "passive"))
    )
    (net (code "72") (name "Net-(IC2A-QH)") (class "Default")
      (node (ref "IC2") (pin "7") (pinfunction "QH_7") (pintype "tri_state"))
      (node (ref "R17") (pin "P$1") (pinfunction "1_P$1") (pintype "passive"))
    )
    (net (code "73") (name "Net-(IC2A-QH*)") (class "Default")
      (node (ref "IC2") (pin "9") (pinfunction "QH*_9") (pintype "tri_state"))
      (node (ref "IC3") (pin "14") (pinfunction "SER_14") (pintype "input"))
    )
    (net (code "74") (name "Net-(IC2A-SCL)") (class "Default")
      (node (ref "IC2") (pin "10") (pinfunction "SCL_10") (pintype "input"))
      (node (ref "R8") (pin "P$2") (pinfunction "2_P$2") (pintype "passive"))
    )
    (net (code "75") (name "Net-(IC3A-G)") (class "Default")
      (node (ref "IC3") (pin "13") (pinfunction "G_13") (pintype "input"))
      (node (ref "R26") (pin "P$2") (pinfunction "2_P$2") (pintype "passive"))
    )
    (net (code "76") (name "Net-(IC3A-QA)") (class "Default")
      (node (ref "IC3") (pin "15") (pinfunction "QA_15") (pintype "tri_state"))
      (node (ref "R25") (pin "P$1") (pinfunction "1_P$1") (pintype "passive"))
    )
    (net (code "77") (name "Net-(IC3A-QB)") (class "Default")
      (node (ref "IC3") (pin "1") (pinfunction "QB_1") (pintype "tri_state"))
      (node (ref "R24") (pin "P$1") (pinfunction "1_P$1") (pintype "passive"))
    )
    (net (code "78") (name "Net-(IC3A-QC)") (class "Default")
      (node (ref "IC3") (pin "2") (pinfunction "QC_2") (pintype "tri_state"))
      (node (ref "R23") (pin "P$1") (pinfunction "1_P$1") (pintype "passive"))
    )
    (net (code "79") (name "Net-(IC3A-QD)") (class "Default")
      (node (ref "IC3") (pin "3") (pinfunction "QD_3") (pintype "tri_state"))
      (node (ref "R21") (pin "P$1") (pinfunction "1_P$1") (pintype "passive"))
    )
    (net (code "80") (name "Net-(IC3A-QE)") (class "Default")
      (node (ref "IC3") (pin "4") (pinfunction "QE_4") (pintype "tri_state"))
      (node (ref "R30") (pin "P$1") (pinfunction "1_P$1") (pintype "passive"))
    )
    (net (code "81") (name "Net-(IC3A-QF)") (class "Default")
      (node (ref "IC3") (pin "5") (pinfunction "QF_5") (pintype "tri_state"))
      (node (ref "R29") (pin "P$1") (pinfunction "1_P$1") (pintype "passive"))
    )
    (net (code "82") (name "Net-(IC3A-QG)") (class "Default")
      (node (ref "IC3") (pin "6") (pinfunction "QG_6") (pintype "tri_state"))
      (node (ref "R28") (pin "P$1") (pinfunction "1_P$1") (pintype "passive"))
    )
    (net (code "83") (name "Net-(IC3A-QH)") (class "Default")
      (node (ref "IC3") (pin "7") (pinfunction "QH_7") (pintype "tri_state"))
      (node (ref "R27") (pin "P$1") (pinfunction "1_P$1") (pintype "passive"))
    )
    (net (code "84") (name "Net-(IC3A-QH*)") (class "Default")
      (node (ref "IC3") (pin "9") (pinfunction "QH*_9") (pintype "tri_state"))
      (node (ref "IC4") (pin "14") (pinfunction "SER_14") (pintype "input"))
    )
    (net (code "85") (name "Net-(IC3A-SCL)") (class "Default")
      (node (ref "IC3") (pin "10") (pinfunction "SCL_10") (pintype "input"))
      (node (ref "R22") (pin "P$2") (pinfunction "2_P$2") (pintype "passive"))
    )
    (net (code "86") (name "Net-(IC4A-G)") (class "Default")
      (node (ref "IC4") (pin "13") (pinfunction "G_13") (pintype "input"))
      (node (ref "R36") (pin "P$2") (pinfunction "2_P$2") (pintype "passive"))
    )
    (net (code "87") (name "Net-(IC4A-QA)") (class "Default")
      (node (ref "IC4") (pin "15") (pinfunction "QA_15") (pintype "tri_state"))
      (node (ref "R35") (pin "P$1") (pinfunction "1_P$1") (pintype "passive"))
    )
    (net (code "88") (name "Net-(IC4A-QB)") (class "Default")
      (node (ref "IC4") (pin "1") (pinfunction "QB_1") (pintype "tri_state"))
      (node (ref "R34") (pin "P$1") (pinfunction "1_P$1") (pintype "passive"))
    )
    (net (code "89") (name "Net-(IC4A-QC)") (class "Default")
      (node (ref "IC4") (pin "2") (pinfunction "QC_2") (pintype "tri_state"))
      (node (ref "R33") (pin "P$1") (pinfunction "1_P$1") (pintype "passive"))
    )
    (net (code "90") (name "Net-(IC4A-QD)") (class "Default")
      (node (ref "IC4") (pin "3") (pinfunction "QD_3") (pintype "tri_state"))
      (node (ref "R31") (pin "P$1") (pinfunction "1_P$1") (pintype "passive"))
    )
    (net (code "91") (name "Net-(IC4A-QE)") (class "Default")
      (node (ref "IC4") (pin "4") (pinfunction "QE_4") (pintype "tri_state"))
      (node (ref "R40") (pin "P$1") (pinfunction "1_P$1") (pintype "passive"))
    )
    (net (code "92") (name "Net-(IC4A-QF)") (class "Default")
      (node (ref "IC4") (pin "5") (pinfunction "QF_5") (pintype "tri_state"))
      (node (ref "R39") (pin "P$1") (pinfunction "1_P$1") (pintype "passive"))
    )
    (net (code "93") (name "Net-(IC4A-QG)") (class "Default")
      (node (ref "IC4") (pin "6") (pinfunction "QG_6") (pintype "tri_state"))
      (node (ref "R38") (pin "P$1") (pinfunction "1_P$1") (pintype "passive"))
    )
    (net (code "94") (name "Net-(IC4A-QH)") (class "Default")
      (node (ref "IC4") (pin "7") (pinfunction "QH_7") (pintype "tri_state"))
      (node (ref "R37") (pin "P$1") (pinfunction "1_P$1") (pintype "passive"))
    )
    (net (code "95") (name "Net-(IC4A-QH*)") (class "Default")
      (node (ref "IC4") (pin "9") (pinfunction "QH*_9") (pintype "tri_state"))
      (node (ref "IC5") (pin "14") (pinfunction "SER_14") (pintype "input"))
    )
    (net (code "96") (name "Net-(IC4A-SCL)") (class "Default")
      (node (ref "IC4") (pin "10") (pinfunction "SCL_10") (pintype "input"))
      (node (ref "R32") (pin "P$2") (pinfunction "2_P$2") (pintype "passive"))
    )
    (net (code "97") (name "Net-(IC5A-G)") (class "Default")
      (node (ref "IC5") (pin "13") (pinfunction "G_13") (pintype "input"))
      (node (ref "R46") (pin "P$2") (pinfunction "2_P$2") (pintype "passive"))
    )
    (net (code "98") (name "Net-(IC5A-QA)") (class "Default")
      (node (ref "IC5") (pin "15") (pinfunction "QA_15") (pintype "tri_state"))
      (node (ref "R45") (pin "P$1") (pinfunction "1_P$1") (pintype "passive"))
    )
    (net (code "99") (name "Net-(IC5A-QB)") (class "Default")
      (node (ref "IC5") (pin "1") (pinfunction "QB_1") (pintype "tri_state"))
      (node (ref "R44") (pin "P$1") (pinfunction "1_P$1") (pintype "passive"))
    )
    (net (code "100") (name "Net-(IC5A-QC)") (class "Default")
      (node (ref "IC5") (pin "2") (pinfunction "QC_2") (pintype "tri_state"))
      (node (ref "R43") (pin "P$1") (pinfunction "1_P$1") (pintype "passive"))
    )
    (net (code "101") (name "Net-(IC5A-QD)") (class "Default")
      (node (ref "IC5") (pin "3") (pinfunction "QD_3") (pintype "tri_state"))
      (node (ref "R41") (pin "P$1") (pinfunction "1_P$1") (pintype "passive"))
    )
    (net (code "102") (name "Net-(IC5A-QE)") (class "Default")
      (node (ref "IC5") (pin "4") (pinfunction "QE_4") (pintype "tri_state"))
      (node (ref "R50") (pin "P$1") (pinfunction "1_P$1") (pintype "passive"))
    )
    (net (code "103") (name "Net-(IC5A-QF)") (class "Default")
      (node (ref "IC5") (pin "5") (pinfunction "QF_5") (pintype "tri_state"))
      (node (ref "R49") (pin "P$1") (pinfunction "1_P$1") (pintype "passive"))
    )
    (net (code "104") (name "Net-(IC5A-QG)") (class "Default")
      (node (ref "IC5") (pin "6") (pinfunction "QG_6") (pintype "tri_state"))
      (node (ref "R48") (pin "P$1") (pinfunction "1_P$1") (pintype "passive"))
    )
    (net (code "105") (name "Net-(IC5A-QH)") (class "Default")
      (node (ref "IC5") (pin "7") (pinfunction "QH_7") (pintype "tri_state"))
      (node (ref "R47") (pin "P$1") (pinfunction "1_P$1") (pintype "passive"))
    )
    (net (code "106") (name "Net-(IC5A-QH*)") (class "Default")
      (node (ref "IC5") (pin "9") (pinfunction "QH*_9") (pintype "tri_state"))
      (node (ref "IC6") (pin "14") (pinfunction "SER_14") (pintype "input"))
    )
    (net (code "107") (name "Net-(IC5A-SCL)") (class "Default")
      (node (ref "IC5") (pin "10") (pinfunction "SCL_10") (pintype "input"))
      (node (ref "R42") (pin "P$2") (pinfunction "2_P$2") (pintype "passive"))
    )
    (net (code "108") (name "Net-(IC6A-G)") (class "Default")
      (node (ref "IC6") (pin "13") (pinfunction "G_13") (pintype "input"))
      (node (ref "R56") (pin "P$2") (pinfunction "2_P$2") (pintype "passive"))
    )
    (net (code "109") (name "Net-(IC6A-QA)") (class "Default")
      (node (ref "IC6") (pin "15") (pinfunction "QA_15") (pintype "tri_state"))
      (node (ref "R55") (pin "P$1") (pinfunction "1_P$1") (pintype "passive"))
    )
    (net (code "110") (name "Net-(IC6A-QB)") (class "Default")
      (node (ref "IC6") (pin "1") (pinfunction "QB_1") (pintype "tri_state"))
      (node (ref "R54") (pin "P$1") (pinfunction "1_P$1") (pintype "passive"))
    )
    (net (code "111") (name "Net-(IC6A-QC)") (class "Default")
      (node (ref "IC6") (pin "2") (pinfunction "QC_2") (pintype "tri_state"))
      (node (ref "R53") (pin "P$1") (pinfunction "1_P$1") (pintype "passive"))
    )
    (net (code "112") (name "Net-(IC6A-QD)") (class "Default")
      (node (ref "IC6") (pin "3") (pinfunction "QD_3") (pintype "tri_state"))
      (node (ref "R51") (pin "P$1") (pinfunction "1_P$1") (pintype "passive"))
    )
    (net (code "113") (name "Net-(IC6A-QE)") (class "Default")
      (node (ref "IC6") (pin "4") (pinfunction "QE_4") (pintype "tri_state"))
      (node (ref "R60") (pin "P$1") (pinfunction "1_P$1") (pintype "passive"))
    )
    (net (code "114") (name "Net-(IC6A-QF)") (class "Default")
      (node (ref "IC6") (pin "5") (pinfunction "QF_5") (pintype "tri_state"))
      (node (ref "R59") (pin "P$1") (pinfunction "1_P$1") (pintype "passive"))
    )
    (net (code "115") (name "Net-(IC6A-QG)") (class "Default")
      (node (ref "IC6") (pin "6") (pinfunction "QG_6") (pintype "tri_state"))
      (node (ref "R58") (pin "P$1") (pinfunction "1_P$1") (pintype "passive"))
    )
    (net (code "116") (name "Net-(IC6A-QH)") (class "Default")
      (node (ref "IC6") (pin "7") (pinfunction "QH_7") (pintype "tri_state"))
      (node (ref "R57") (pin "P$1") (pinfunction "1_P$1") (pintype "passive"))
    )
    (net (code "117") (name "Net-(IC6A-SCL)") (class "Default")
      (node (ref "IC6") (pin "10") (pinfunction "SCL_10") (pintype "input"))
      (node (ref "R52") (pin "P$2") (pinfunction "2_P$2") (pintype "passive"))
    )
    (net (code "118") (name "VCC") (class "Default")
      (node (ref "J1") (pin "5") (pinfunction "5_5") (pintype "passive"))
      (node (ref "R22") (pin "P$1") (pinfunction "1_P$1") (pintype "passive"))
      (node (ref "R3") (pin "P$1") (pinfunction "1_P$1") (pintype "passive"))
      (node (ref "R32") (pin "P$1") (pinfunction "1_P$1") (pintype "passive"))
      (node (ref "R42") (pin "P$1") (pinfunction "1_P$1") (pintype "passive"))
      (node (ref "R52") (pin "P$1") (pinfunction "1_P$1") (pintype "passive"))
      (node (ref "R8") (pin "P$1") (pinfunction "1_P$1") (pintype "passive"))
    )
    (net (code "119") (name "unconnected-(IC6A-QH*-Pad9)") (class "Default")
      (node (ref "IC6") (pin "9") (pinfunction "QH*_9") (pintype "tri_state"))
    )
  )
)
